# Time_Management.net
KiCad netlist of a schematic drawn in Altium Designer
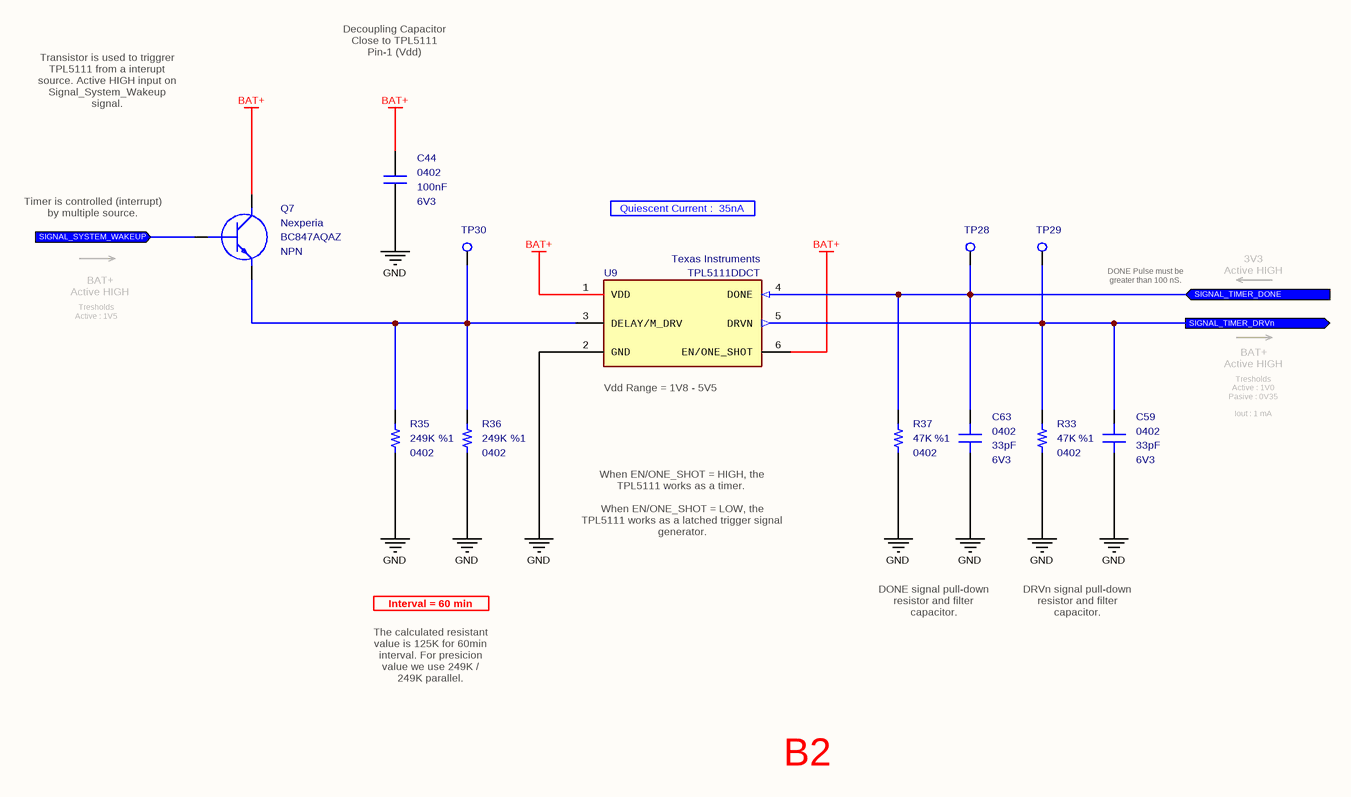
[diagram p0: Time Management.SchDoc]

(export (version "E")
  (design (tool "Eeschema 10.0.6"))
  (components
    (comp (ref "C44")
      (value "100nF")
      (footprint "CAPACITOR_0402")
      (description "Capacitor - 100nF [0402-6V3] (Ceramic)")
      (fields
        (field (name "MANUFACTURER_PART_NUMBER") "04026D104KAT4A")
        (field (name "MOUSER_PART_NUMBER") "581-04026D104KAT4A")
        (field (name "CASE") "0402")
        (field (name "VOLTAGE") "6V3")
      )
      (libsource (lib "Ovoo_Schematic") (part "Capacitor - 100nF [0402-6V3]"))
    )
    (comp (ref "C59")
      (value "33pF")
      (footprint "CAPACITOR_0402")
      (description "Capacitor - 33pF [0402] (Ceramic)")
      (fields
        (field (name "MANUFACTURER_PART_NUMBER") "C0402C330J9RACAUTO")
        (field (name "MOUSER_PART_NUMBER") "80-C0402C330J9RAUTO")
        (field (name "CASE") "0402")
        (field (name "VOLTAGE") "6V3")
      )
      (libsource (lib "Ovoo_Schematic") (part "Capacitor - 33pF [0402-6V3]"))
    )
    (comp (ref "C63")
      (value "33pF")
      (footprint "CAPACITOR_0402")
      (description "Capacitor - 33pF [0402] (Ceramic)")
      (fields
        (field (name "MANUFACTURER_PART_NUMBER") "C0402C330J9RACAUTO")
        (field (name "MOUSER_PART_NUMBER") "80-C0402C330J9RAUTO")
        (field (name "CASE") "0402")
        (field (name "VOLTAGE") "6V3")
      )
      (libsource (lib "Ovoo_Schematic") (part "Capacitor - 33pF [0402-6V3]"))
    )
    (comp (ref "Q7")
      (value "Bipolar NPN Transistors")
      (footprint "SOT1215")
      (description "Bipolar Transistors - BJT BC847AQA/DFN1010D-3/REEL 7\" Q2")
      (fields
        (field (name "MOUSER_PART_NUMBER") "771-BC847AQAZ")
        (field (name "MANUFACTURER_NAME") "Nexperia")
        (field (name "MANUFACTURER_PART_NUMBER") "BC847AQAZ")
        (field (name "POLARITY") "NPN")
      )
      (libsource (lib "Ovoo_Schematic") (part "Transistor - BC847"))
    )
    (comp (ref "R33")
      (value "47K")
      (footprint "RESISTOR_0402")
      (description "Thick Film Resistors - SMD 1/16 W 47 Kohms 1%")
      (fields
        (field (name "MANUFACTURER_PART_NUMBER") "CRCW040247K0FKED")
        (field (name "MOUSER_PART_NUMBER") "71-CRCW0402-47K-E3")
        (field (name "TOLERANCE") "%1")
        (field (name "CASE") "0402")
      )
      (libsource (lib "Ovoo_Schematic") (part "Resistor - 47K"))
    )
    (comp (ref "R35")
      (value "249K")
      (footprint "RESISTOR_0402")
      (description "Thick Film Resistors - SMD 1/16 W 249 Kohms 1%")
      (fields
        (field (name "MANUFACTURER_PART_NUMBER") "CRCW0402249KFKED")
        (field (name "MOUSER_PART_NUMBER") "71-CRCW0402-249K-E3")
        (field (name "TOLERANCE") "%1")
        (field (name "CASE") "0402")
      )
      (libsource (lib "Ovoo_Schematic") (part "Resistor - 249K"))
    )
    (comp (ref "R36")
      (value "249K")
      (footprint "RESISTOR_0402")
      (description "Thick Film Resistors - SMD 1/16 W 249 Kohms 1%")
      (fields
        (field (name "MANUFACTURER_PART_NUMBER") "CRCW0402249KFKED")
        (field (name "MOUSER_PART_NUMBER") "71-CRCW0402-249K-E3")
        (field (name "TOLERANCE") "%1")
        (field (name "CASE") "0402")
      )
      (libsource (lib "Ovoo_Schematic") (part "Resistor - 249K"))
    )
    (comp (ref "R37")
      (value "47K")
      (footprint "RESISTOR_0402")
      (description "Thick Film Resistors - SMD 1/16 W 47 Kohms 1%")
      (fields
        (field (name "MANUFACTURER_PART_NUMBER") "CRCW040247K0FKED")
        (field (name "MOUSER_PART_NUMBER") "71-CRCW0402-47K-E3")
        (field (name "TOLERANCE") "%1")
        (field (name "CASE") "0402")
      )
      (libsource (lib "Ovoo_Schematic") (part "Resistor - 47K"))
    )
    (comp (ref "TP28")
      (value "PCB - Test Point")
      (footprint "Test_Pad - Hole")
      (description "Test Point")
      (libsource (lib "Ovoo_Schematic") (part "PCB - Test Point"))
    )
    (comp (ref "TP29")
      (value "PCB - Test Point")
      (footprint "Test_Pad - Hole")
      (description "Test Point")
      (libsource (lib "Ovoo_Schematic") (part "PCB - Test Point"))
    )
    (comp (ref "TP30")
      (value "PCB - Test Point")
      (footprint "Test_Pad - Hole")
      (description "Test Point")
      (libsource (lib "Ovoo_Schematic") (part "PCB - Test Point"))
    )
    (comp (ref "U9")
      (value "Nanopower Timer IC")
      (footprint "SOT-23-6")
      (fields
        (field (name "MOUSER_PART_NUMBER") "595-TPL5111DDCT")
        (field (name "MANUFACTURER _PART_NUMBER") "TPL5111DDCT")
        (field (name "MANUFACTURER_NAME") "Texas Instruments")
      )
      (libsource (lib "Ovoo_Schematic") (part "IC - TPL5111"))
    )
  )
  (nets
    (net (code "1") (name "/SIGNAL_SYSTEM_WAKEUP") (class "Default")
      (node (ref "Q7") (pin "1") (pinfunction "B_1") (pintype "passive"))
    )
    (net (code "2") (name "/SIGNAL_TIMER_DONE") (class "Default")
      (node (ref "C63") (pin "2") (pinfunction "2_2") (pintype "passive"))
      (node (ref "R37") (pin "2") (pinfunction "2_2") (pintype "passive"))
      (node (ref "TP28") (pin "1") (pinfunction "1_1") (pintype "passive"))
      (node (ref "U9") (pin "4") (pinfunction "DONE_4") (pintype "input"))
    )
    (net (code "3") (name "/SIGNAL_TIMER_DRVn") (class "Default")
      (node (ref "C59") (pin "2") (pinfunction "2_2") (pintype "passive"))
      (node (ref "R33") (pin "2") (pinfunction "2_2") (pintype "passive"))
      (node (ref "TP29") (pin "1") (pinfunction "1_1") (pintype "passive"))
      (node (ref "U9") (pin "5") (pinfunction "DRVN_5") (pintype "output"))
    )
    (net (code "4") (name "BAT+") (class "Default")
      (node (ref "C44") (pin "2") (pinfunction "2_2") (pintype "passive"))
      (node (ref "Q7") (pin "3") (pinfunction "C_3") (pintype "passive"))
      (node (ref "U9") (pin "1") (pinfunction "VDD_1") (pintype "power_in"))
      (node (ref "U9") (pin "6") (pinfunction "EN/ONE_SHOT_6") (pintype "passive"))
    )
    (net (code "5") (name "GND") (class "Default")
      (node (ref "C44") (pin "1") (pinfunction "1_1") (pintype "passive"))
      (node (ref "C59") (pin "1") (pinfunction "1_1") (pintype "passive"))
      (node (ref "C63") (pin "1") (pinfunction "1_1") (pintype "passive"))
      (node (ref "R33") (pin "1") (pinfunction "1_1") (pintype "passive"))
      (node (ref "R35") (pin "1") (pinfunction "1_1") (pintype "passive"))
      (node (ref "R36") (pin "1") (pinfunction "1_1") (pintype "passive"))
      (node (ref "R37") (pin "1") (pinfunction "1_1") (pintype "passive"))
      (node (ref "U9") (pin "2") (pinfunction "GND_2") (pintype "power_in"))
    )
    (net (code "6") (name "Net-(Q7-E)") (class "Default")
      (node (ref "Q7") (pin "2") (pinfunction "E_2") (pintype "passive"))
      (node (ref "R35") (pin "2") (pinfunction "2_2") (pintype "passive"))
      (node (ref "R36") (pin "2") (pinfunction "2_2") (pintype "passive"))
      (node (ref "TP30") (pin "1") (pinfunction "1_1") (pintype "passive"))
      (node (ref "U9") (pin "3") (pinfunction "DELAY/M_DRV_3") (pintype "passive"))
    )
  )
)
